# L6225_MotorDriver.net
KiCad netlist of a schematic drawn in Altium Designer
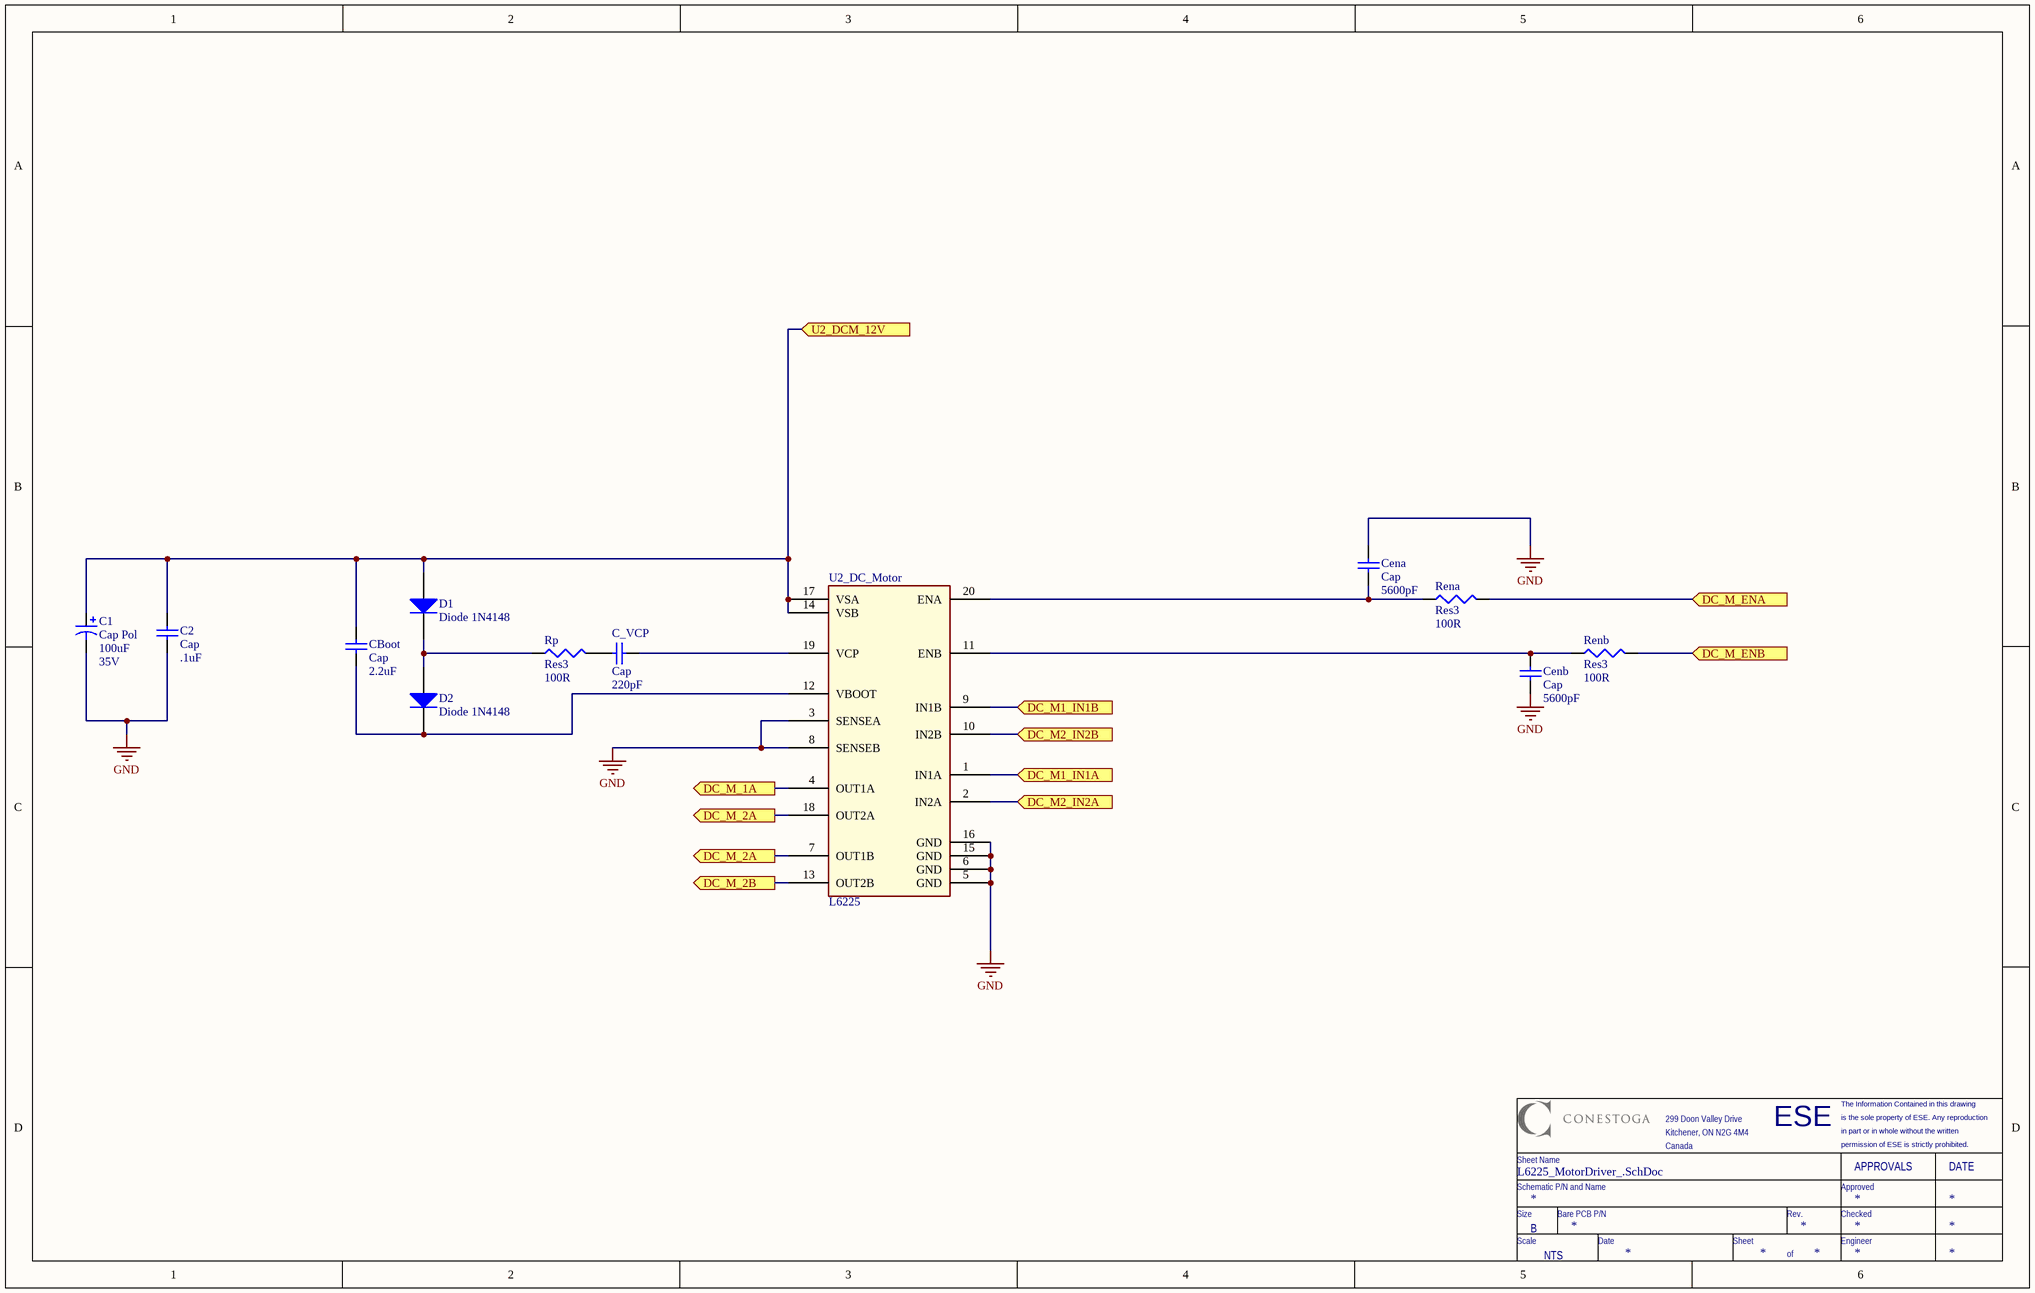
[diagram p0: L6225_MotorDriver_.SchDoc]

(export (version "E")
  (design (tool "Eeschema 10.0.6"))
  (components
    (comp (ref "C1")
      (value "Cap Pol")
      (footprint "CAPACITOR_6.3MM")
      (description "CAP 85C 100uF ±20% 16V WX Series Aluminum Electrolytic")
      (fields
        (field (name "ALTIUM_VALUE") "100uF")
        (field (name "VOLTAGE") "35V")
        (field (name "MPN") "UWX1C101MCL1GB")
      )
      (libsource (lib "esd_library") (part "Cap Polar-100uF-16V"))
    )
    (comp (ref "C2")
      (value "Cap")
      (footprint "CAPC2012X09M")
      (description "CAP CER .1uF 100v X7R 0805")
      (fields (field (name "ALTIUM_VALUE") ".1uF") (field (name "MPN") "C0805C104K1RACTU"))
      (libsource (lib "esd_library") (part "CAP-X7R-.1uF-100V-±10%"))
    )
    (comp (ref "CBoot")
      (value "Cap")
      (footprint "CAPC2012X09M")
      (description "CAP CER 2.2uF 16v X7R 0805")
      (fields (field (name "ALTIUM_VALUE") "2.2uF") (field (name "MPN") "C0805C225K4RACTU"))
      (libsource (lib "esd_library") (part "CAP-X7R-2.2uF-16V-±10%"))
    )
    (comp (ref "Cena")
      (value "Cap")
      (footprint "CAPC2012X09M")
      (description "CAP CER 5600pF 50v X7R 0805")
      (fields (field (name "ALTIUM_VALUE") "5600pF") (field (name "MPN") "C0805C562K5RACTU"))
      (libsource (lib "esd_library") (part "CAP-X7R-5600pF-50V-±10%"))
    )
    (comp (ref "Cenb")
      (value "Cap")
      (footprint "CAPC2012X09M")
      (description "CAP CER 5600pF 50v X7R 0805")
      (fields (field (name "ALTIUM_VALUE") "5600pF") (field (name "MPN") "C0805C562K5RACTU"))
      (libsource (lib "esd_library") (part "CAP-X7R-5600pF-50V-±10%"))
    )
    (comp (ref "C_VCP")
      (value "Cap")
      (footprint "CAPC2012X09M")
      (description "CAP CER 220pF 50v COG 0805")
      (fields (field (name "ALTIUM_VALUE") "220pF") (field (name "MPN") "C0805C221J5GACTU"))
      (libsource (lib "Caps$") (part "CAP-COG-220pF-50V-±5%"))
    )
    (comp (ref "D1")
      (value "Diode 1N4148")
      (footprint "zener_sod323")
      (description "High Conductance Fast Diode")
      (libsource (lib "esd_library") (part "Diode 1N4148"))
    )
    (comp (ref "D2")
      (value "Diode 1N4148")
      (footprint "zener_sod323")
      (description "High Conductance Fast Diode")
      (libsource (lib "esd_library") (part "Diode 1N4148"))
    )
    (comp (ref "Rena")
      (value "Res3")
      (footprint "RESC2112X05M")
      (description "RES SMD 100R OHM 1% 1/8W 0805")
      (fields (field (name "ALTIUM_VALUE") "100R") (field (name "MPN") "CRCW0805100RFKEA"))
      (libsource (lib "esd_library") (part "Resistor_100R"))
    )
    (comp (ref "Renb")
      (value "Res3")
      (footprint "RESC2112X05M")
      (description "RES SMD 100R OHM 1% 1/8W 0805")
      (fields (field (name "ALTIUM_VALUE") "100R") (field (name "MPN") "CRCW0805100RFKEA"))
      (libsource (lib "esd_library") (part "Resistor_100R"))
    )
    (comp (ref "Rp")
      (value "Res3")
      (footprint "RESC2112X05M")
      (description "RES SMD 100R OHM 1% 1/8W 0805")
      (fields (field (name "ALTIUM_VALUE") "100R") (field (name "MPN") "CRCW0805100RFKEA"))
      (libsource (lib "esd_library") (part "Resistor_100R"))
    )
    (comp (ref "U2_DC_Motor")
      (value "L6225")
      (footprint "POWERSOP20")
      (description "IC MOTOR DRIVER PAR 20POWERSO")
      (fields (field (name "MPN") "L6225PDTR"))
      (libsource (lib "esd_library") (part "L6225"))
    )
  )
  (nets
    (net (code "1") (name "/DC_M1_IN1A") (class "Default")
      (node (ref "U2_DC_Motor") (pin "1") (pinfunction "IN1A_1") (pintype "passive"))
    )
    (net (code "2") (name "/DC_M1_IN1B") (class "Default")
      (node (ref "U2_DC_Motor") (pin "9") (pinfunction "IN1B_9") (pintype "passive"))
    )
    (net (code "3") (name "/DC_M2_IN2A") (class "Default")
      (node (ref "U2_DC_Motor") (pin "2") (pinfunction "IN2A_2") (pintype "passive"))
    )
    (net (code "4") (name "/DC_M2_IN2B") (class "Default")
      (node (ref "U2_DC_Motor") (pin "10") (pinfunction "IN2B_10") (pintype "passive"))
    )
    (net (code "5") (name "/DC_M_1A") (class "Default")
      (node (ref "U2_DC_Motor") (pin "4") (pinfunction "OUT1A_4") (pintype "passive"))
    )
    (net (code "6") (name "/DC_M_2A") (class "Default")
      (node (ref "U2_DC_Motor") (pin "18") (pinfunction "OUT2A_18") (pintype "passive"))
      (node (ref "U2_DC_Motor") (pin "7") (pinfunction "OUT1B_7") (pintype "passive"))
    )
    (net (code "7") (name "/DC_M_2B") (class "Default")
      (node (ref "U2_DC_Motor") (pin "13") (pinfunction "OUT2B_13") (pintype "passive"))
    )
    (net (code "8") (name "/DC_M_ENA") (class "Default")
      (node (ref "Rena") (pin "2") (pinfunction "2_2") (pintype "passive"))
    )
    (net (code "9") (name "/DC_M_ENB") (class "Default")
      (node (ref "Renb") (pin "2") (pinfunction "2_2") (pintype "passive"))
    )
    (net (code "10") (name "/U2_DCM_12V") (class "Default")
      (node (ref "C1") (pin "1") (pinfunction "1_1") (pintype "passive"))
      (node (ref "C2") (pin "2") (pinfunction "2_2") (pintype "passive"))
      (node (ref "CBoot") (pin "2") (pinfunction "2_2") (pintype "passive"))
      (node (ref "D1") (pin "A") (pinfunction "A_A") (pintype "passive"))
      (node (ref "U2_DC_Motor") (pin "14") (pinfunction "VSB_14") (pintype "power_in"))
      (node (ref "U2_DC_Motor") (pin "17") (pinfunction "VSA_17") (pintype "power_in"))
    )
    (net (code "11") (name "GND") (class "Default")
      (node (ref "C1") (pin "2") (pinfunction "2_2") (pintype "passive"))
      (node (ref "C2") (pin "1") (pinfunction "1_1") (pintype "passive"))
      (node (ref "Cena") (pin "2") (pinfunction "2_2") (pintype "passive"))
      (node (ref "Cenb") (pin "1") (pinfunction "1_1") (pintype "passive"))
      (node (ref "U2_DC_Motor") (pin "15") (pinfunction "GND_15") (pintype "power_in"))
      (node (ref "U2_DC_Motor") (pin "16") (pinfunction "GND_16") (pintype "power_in"))
      (node (ref "U2_DC_Motor") (pin "3") (pinfunction "SENSEA_3") (pintype "open_collector"))
      (node (ref "U2_DC_Motor") (pin "5") (pinfunction "GND_5") (pintype "power_in"))
      (node (ref "U2_DC_Motor") (pin "6") (pinfunction "GND_6") (pintype "power_in"))
      (node (ref "U2_DC_Motor") (pin "8") (pinfunction "SENSEB_8") (pintype "power_in"))
    )
    (net (code "12") (name "Net-(C_VCP-Pad1)") (class "Default")
      (node (ref "C_VCP") (pin "1") (pinfunction "1_1") (pintype "passive"))
      (node (ref "Rp") (pin "2") (pinfunction "2_2") (pintype "passive"))
    )
    (net (code "13") (name "Net-(D1-PadK)") (class "Default")
      (node (ref "D1") (pin "K") (pinfunction "K_K") (pintype "passive"))
      (node (ref "D2") (pin "A") (pinfunction "A_A") (pintype "passive"))
      (node (ref "Rp") (pin "1") (pinfunction "1_1") (pintype "passive"))
    )
    (net (code "14") (name "Net-(U2_DC_Motor-ENA)") (class "Default")
      (node (ref "Cena") (pin "1") (pinfunction "1_1") (pintype "passive"))
      (node (ref "Rena") (pin "1") (pinfunction "1_1") (pintype "passive"))
      (node (ref "U2_DC_Motor") (pin "20") (pinfunction "ENA_20") (pintype "passive"))
    )
    (net (code "15") (name "Net-(U2_DC_Motor-ENB)") (class "Default")
      (node (ref "Cenb") (pin "2") (pinfunction "2_2") (pintype "passive"))
      (node (ref "Renb") (pin "1") (pinfunction "1_1") (pintype "passive"))
      (node (ref "U2_DC_Motor") (pin "11") (pinfunction "ENB_11") (pintype "passive"))
    )
    (net (code "16") (name "Net-(U2_DC_Motor-VBOOT)") (class "Default")
      (node (ref "CBoot") (pin "1") (pinfunction "1_1") (pintype "passive"))
      (node (ref "D2") (pin "K") (pinfunction "K_K") (pintype "passive"))
      (node (ref "U2_DC_Motor") (pin "12") (pinfunction "VBOOT_12") (pintype "power_in"))
    )
    (net (code "17") (name "Net-(U2_DC_Motor-VCP)") (class "Default")
      (node (ref "C_VCP") (pin "2") (pinfunction "2_2") (pintype "passive"))
      (node (ref "U2_DC_Motor") (pin "19") (pinfunction "VCP_19") (pintype "power_in"))
    )
  )
)
